# 600_v1_0.net
KiCad netlist of a schematic drawn in Altium Designer
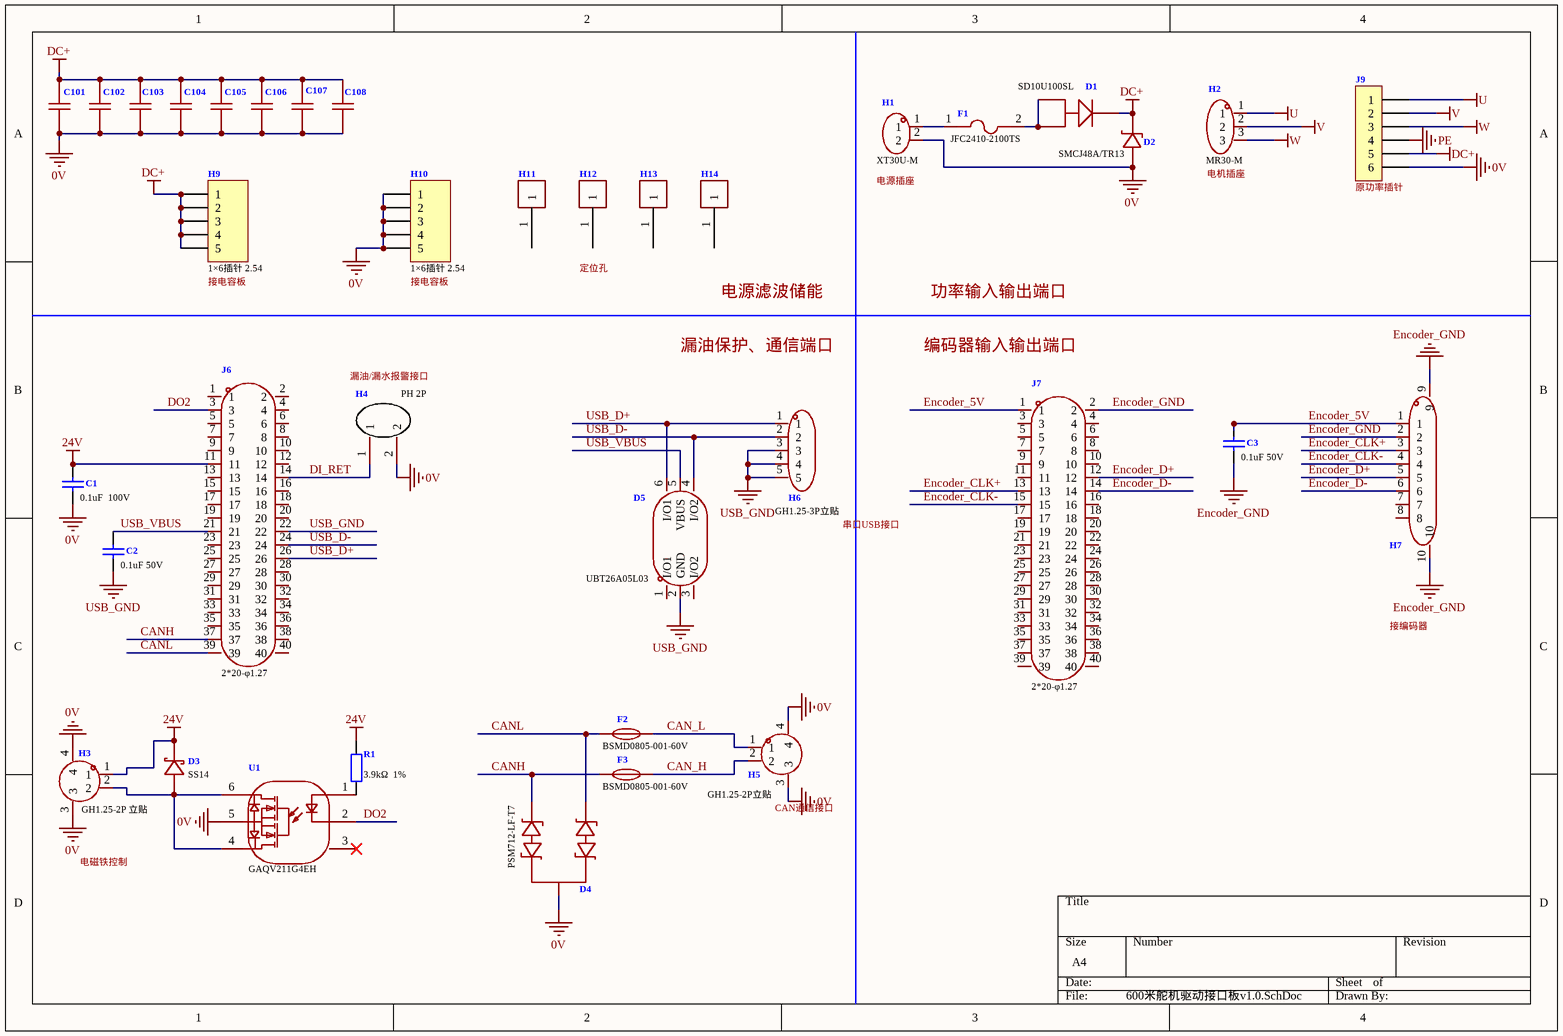
[diagram p0: 600米舵机驱动接口板v1.0.SchDoc]

(export (version "E")
  (design (tool "Eeschema 10.0.6"))
  (components
    (comp (ref "C1")
      (value "0.1uF  100V")
      (footprint "0805_C")
      (description "贴片电容")
      (libsource (lib "Miscellaneous Devices LC") (part "0805 1uF (105) 10% 50V"))
    )
    (comp (ref "C2")
      (value "0.1uF 50V")
      (footprint "0805_C")
      (description "贴片电容")
      (libsource (lib "Miscellaneous Devices LC") (part "0805 1uF (105) 10% 50V"))
    )
    (comp (ref "C3")
      (value "0.1uF 50V")
      (footprint "0805_C")
      (description "贴片电容")
      (libsource (lib "Miscellaneous Devices LC") (part "0805 1uF (105) 10% 50V"))
    )
    (comp (ref "C101")
      (value "4.7uf 100V")
      (footprint "1210_C")
      (description "贴片电容")
      (fields (field (name "MANUFACTURER") "FH(风华)") (field (name "MANUFACTURER PART") "1210B475K101NT"))
      (libsource (lib "Schlib1") (part "1210 4.7uf"))
    )
    (comp (ref "C102")
      (value "4.7uf 100V")
      (footprint "1210_C")
      (description "贴片电容")
      (fields (field (name "MANUFACTURER") "FH(风华)") (field (name "MANUFACTURER PART") "1210B475K101NT"))
      (libsource (lib "Schlib1") (part "1210 4.7uf"))
    )
    (comp (ref "C103")
      (value "4.7uf 100V")
      (footprint "1210_C")
      (description "贴片电容")
      (fields (field (name "MANUFACTURER") "FH(风华)") (field (name "MANUFACTURER PART") "1210B475K101NT"))
      (libsource (lib "Schlib1") (part "1210 4.7uf"))
    )
    (comp (ref "C104")
      (value "4.7uf 100V")
      (footprint "1210_C")
      (description "贴片电容")
      (fields (field (name "MANUFACTURER") "FH(风华)") (field (name "MANUFACTURER PART") "1210B475K101NT"))
      (libsource (lib "Schlib1") (part "1210 4.7uf"))
    )
    (comp (ref "C105")
      (value "4.7uf 100V")
      (footprint "1210_C")
      (description "贴片电容")
      (fields (field (name "MANUFACTURER") "FH(风华)") (field (name "MANUFACTURER PART") "1210B475K101NT"))
      (libsource (lib "Schlib1") (part "1210 4.7uf"))
    )
    (comp (ref "C106")
      (value "4.7uf 100V")
      (footprint "1210_C")
      (description "贴片电容")
      (fields (field (name "MANUFACTURER") "FH(风华)") (field (name "MANUFACTURER PART") "1210B475K101NT"))
      (libsource (lib "Schlib1") (part "1210 4.7uf"))
    )
    (comp (ref "C107")
      (value "4.7uf 100V")
      (footprint "1210_C")
      (description "贴片电容")
      (fields (field (name "MANUFACTURER") "FH(风华)") (field (name "MANUFACTURER PART") "1210B475K101NT"))
      (libsource (lib "Schlib1") (part "1210 4.7uf"))
    )
    (comp (ref "C108")
      (value "4.7uf 100V")
      (footprint "1210_C")
      (description "贴片电容")
      (fields (field (name "MANUFACTURER") "FH(风华)") (field (name "MANUFACTURER PART") "1210B475K101NT"))
      (libsource (lib "Schlib1") (part "1210 4.7uf"))
    )
    (comp (ref "D1")
      (value "SD10U100SL")
      (footprint "TO-227B-SMD_L6.1-W4.3-LS7.0-RD")
      (description "肖特基二极管")
      (fields (field (name "MANUFACTURER") "LGE(鲁光)"))
      (libsource (lib "二极管稳压等") (part "SD10U100SL"))
    )
    (comp (ref "D2")
      (value "SMCJ48A/TR13")
      (footprint "SMC_L7.1-W6.2-LS8.1-FD")
      (description "TVS")
      (fields (field (name "MANUFACTURER") "Brightking(君耀电子)"))
      (libsource (lib "二极管稳压等") (part "SMCJ48A/TR13"))
    )
    (comp (ref "D3")
      (value "SS14")
      (footprint "SMAF_L3.5-W2.6-LS4.7-FD")
      (fields (field (name "MANUFACTURER") "GOODWORK(固得沃克)") (field (name "MANUFACTURER PART") "SS34F"))
      (libsource (lib "Schlib1") (part "SS34F_C908669"))
    )
    (comp (ref "D4")
      (value "PSM712-LF-T7")
      (footprint "SOT-23(SOT-23-3)")
      (description "双向TVS")
      (fields (field (name "MANUFACTURER") "PROTEK"))
      (libsource (lib "二极管稳压等") (part "PSM712-LF-T7"))
    )
    (comp (ref "D5")
      (value "UBT26A05L03")
      (footprint "SOT-23-6_L2.9-W1.6-P0.95-LS2.8-BR")
      (description "TVS")
      (fields (field (name "MANUFACTURER") "Brightking(君耀电子)"))
      (libsource (lib "二极管稳压等") (part "UBT26A05L03"))
    )
    (comp (ref "F1")
      (value "JFC2410-2100TS")
      (footprint "F2410")
      (description "保险管")
      (fields (field (name "MANUFACTURER") "JDTfuse(集电通)"))
      (libsource (lib "保险") (part "JFC2410-2100TS"))
    )
    (comp (ref "F2")
      (value "BSMD0805-001-60V")
      (footprint "F0805")
      (description "自恢复保险")
      (fields (field (name "MANUFACTURER") "BHFUSE(佰宏)"))
      (libsource (lib "保险") (part "BSMD0805-001-60V"))
    )
    (comp (ref "F3")
      (value "BSMD0805-001-60V")
      (footprint "F0805")
      (description "自恢复保险")
      (fields (field (name "MANUFACTURER") "BHFUSE(佰宏)"))
      (libsource (lib "保险") (part "BSMD0805-001-60V"))
    )
    (comp (ref "H1")
      (value "XT30U-M")
      (footprint "CONN-TH_XT30U-M-PCB")
      (fields (field (name "MANUFACTURER") "AMASS(艾迈斯)"))
      (libsource (lib "Header") (part "XT30U-M"))
    )
    (comp (ref "H2")
      (value "MR30-M")
      (footprint "CONN-TH_MR30-M-PCB")
      (fields (field (name "MANUFACTURER") "AMASS(艾迈斯)"))
      (libsource (lib "Header") (part "MR30-M"))
    )
    (comp (ref "H3")
      (value "GH1.25-2P 立贴")
      (footprint "CONN-TH_2P-P1.25_XUNPU_WAFER-GH1.25-2PLB")
      (fields
        (field (name "MANUFACTURER") "XUNPU(讯普)")
        (field (name "MANUFACTURER PART") "WAFER-GH1.25-2PLB")
      )
      (libsource (lib "Header") (part "WAFER-GH1.25-2PLB"))
    )
    (comp (ref "H4")
      (value "PH 2P")
      (footprint "CONN-TH_B2B-PH-K-S")
      (description "端子")
      (fields (field (name "MANUFACTURER") "JST") (field (name "MANUFACTURER PART") "B2B-PH-K-S(LF)(SN)"))
      (libsource (lib "Header") (part "PH2.0-2P"))
    )
    (comp (ref "H5")
      (value "GH1.25-2P立贴")
      (footprint "CONN-TH_2P-P1.25_XUNPU_WAFER-GH1.25-2PLB")
      (description "连接器")
      (fields
        (field (name "MANUFACTURER") "XUNPU(讯普)")
        (field (name "MANUFACTURER PART") "WAFER-GH1.25-2PLB")
      )
      (libsource (lib "Header") (part "WAFER-GH1.25-2PLB"))
    )
    (comp (ref "H6")
      (value "GH1.25-3P立贴")
      (footprint "CONN-SMD_3P-P1.25_GH1.25-3PLTPZ")
      (description "连接器")
      (fields
        (field (name "MANUFACTURER") "BOOMELE(博穆精密)")
        (field (name "MANUFACTURER PART") "GH1.25-3PLTPZ")
      )
      (libsource (lib "Header") (part "GH1.25-3PLTPZ"))
    )
    (comp (ref "H7")
      (value "SM08B-SURS-TF(LF)(SN)")
      (footprint "CONN-SMD_SM08B-SURS-TF")
      (description "连接器")
      (fields (field (name "MANUFACTURER") "JST"))
      (libsource (lib "Header") (part "SM08B-SURS-TF(LF)(SN)"))
    )
    (comp (ref "H9")
      (value "1×6插针 2.54")
      (footprint "HDR1X5")
      (description "Header, 5-Pin")
      (fields (field (name "PUBLISHER") "Altium Limited"))
      (libsource (lib "Miscellaneous Connectors") (part "Header 5"))
    )
    (comp (ref "H10")
      (value "1×6插针 2.54")
      (footprint "HDR1X5")
      (description "Header, 5-Pin")
      (fields (field (name "PUBLISHER") "Altium Limited"))
      (libsource (lib "Miscellaneous Connectors") (part "Header 5"))
    )
    (comp (ref "H11") (value "定位孔") (footprint "Hole-2.5×3.5") (libsource (lib "Other") (part "Hole")))
    (comp (ref "H12") (value "定位孔") (footprint "Hole-2.5×3.5") (libsource (lib "Other") (part "Hole")))
    (comp (ref "H13") (value "定位孔") (footprint "Hole-2.5×3.5") (libsource (lib "Other") (part "Hole")))
    (comp (ref "H14") (value "定位孔") (footprint "Hole-2.5×3.5") (libsource (lib "Other") (part "Hole")))
    (comp (ref "J6")
      (value "2*20-φ1.27")
      (footprint "HDR-TH_40P-P1.27-V-M-R2-C20-S1.27-ISMC")
      (description "插针孔")
      (fields (field (name "MANUFACTURER") "BOOMELE(博穆精密)") (field (name "MANUFACTURER PART") "2.0-2*20PM"))
      (libsource (lib "Schlib1") (part "2.0-2*20PM"))
    )
    (comp (ref "J7")
      (value "2*20-φ1.27")
      (footprint "HDR-TH_40P-P1.27-V-M-R2-C20-S1.27-ISMC")
      (description "插针孔")
      (fields (field (name "MANUFACTURER") "BOOMELE(博穆精密)") (field (name "MANUFACTURER PART") "2.0-2*20PM"))
      (libsource (lib "Schlib1") (part "2.0-2*20PM"))
    )
    (comp (ref "J9")
      (value "φ1.3")
      (footprint "ISMC_Power")
      (description "插针孔")
      (libsource (lib "Header") (part "Pin HDR1X6"))
    )
    (comp (ref "R1")
      (value "3.9kΩ  1%")
      (footprint "0805_R")
      (description "贴片电阻")
      (libsource (lib "电阻") (part "0805 82Ω (82R0) 1%"))
    )
    (comp (ref "U1")
      (value "GAQV211G4EH")
      (footprint "SMD-6_L8.8-W6.4-P2.54-LS9.6-BL")
      (fields (field (name "MANUFACTURER") "SUPSiC(国晶微半导体)"))
      (libsource (lib "继电器") (part "GAQV211G4EH"))
    )
  )
  (nets
    (net (code "1") (name "/CANH") (class "Default")
      (node (ref "D4") (pin "2") (pinfunction "A1_2") (pintype "passive"))
      (node (ref "F3") (pin "1") (pinfunction "1_1") (pintype "passive"))
      (node (ref "J6") (pin "37") (pinfunction "37_37") (pintype "passive"))
    )
    (net (code "2") (name "/CANL") (class "Default")
      (node (ref "D4") (pin "1") (pinfunction "A1_1") (pintype "passive"))
      (node (ref "F2") (pin "1") (pinfunction "1_1") (pintype "passive"))
      (node (ref "J6") (pin "39") (pinfunction "39_39") (pintype "passive"))
    )
    (net (code "3") (name "/CAN_H") (class "Default")
      (node (ref "F3") (pin "2") (pinfunction "2_2") (pintype "passive"))
      (node (ref "H5") (pin "2") (pinfunction "2_2") (pintype "passive"))
    )
    (net (code "4") (name "/CAN_L") (class "Default")
      (node (ref "F2") (pin "2") (pinfunction "2_2") (pintype "passive"))
      (node (ref "H5") (pin "1") (pinfunction "1_1") (pintype "passive"))
    )
    (net (code "5") (name "/DI_RET") (class "Default")
      (node (ref "H4") (pin "1") (pinfunction "1_1") (pintype "passive"))
      (node (ref "J6") (pin "14") (pinfunction "14_14") (pintype "passive"))
    )
    (net (code "6") (name "/DO2") (class "Default")
      (node (ref "J6") (pin "3") (pinfunction "3_3") (pintype "passive"))
      (node (ref "U1") (pin "2") (pinfunction "2_2") (pintype "passive"))
    )
    (net (code "7") (name "/Encoder_5V") (class "Default")
      (node (ref "C3") (pin "2") (pinfunction "2_2") (pintype "passive"))
      (node (ref "H7") (pin "1") (pinfunction "1_1") (pintype "passive"))
      (node (ref "J7") (pin "1") (pinfunction "1_1") (pintype "passive"))
    )
    (net (code "8") (name "/Encoder_CLK+") (class "Default")
      (node (ref "H7") (pin "3") (pinfunction "3_3") (pintype "passive"))
      (node (ref "J7") (pin "13") (pinfunction "13_13") (pintype "passive"))
    )
    (net (code "9") (name "/Encoder_CLK-") (class "Default")
      (node (ref "H7") (pin "4") (pinfunction "4_4") (pintype "passive"))
      (node (ref "J7") (pin "15") (pinfunction "15_15") (pintype "passive"))
    )
    (net (code "10") (name "/Encoder_D+") (class "Default")
      (node (ref "H7") (pin "5") (pinfunction "5_5") (pintype "passive"))
      (node (ref "J7") (pin "12") (pinfunction "12_12") (pintype "passive"))
    )
    (net (code "11") (name "/Encoder_D-") (class "Default")
      (node (ref "H7") (pin "6") (pinfunction "6_6") (pintype "passive"))
      (node (ref "J7") (pin "14") (pinfunction "14_14") (pintype "passive"))
    )
    (net (code "12") (name "/USB_D+") (class "Default")
      (node (ref "D5") (pin "6") (pinfunction "I/O1_6") (pintype "passive"))
      (node (ref "H6") (pin "1") (pinfunction "1_1") (pintype "passive"))
      (node (ref "J6") (pin "26") (pinfunction "26_26") (pintype "passive"))
    )
    (net (code "13") (name "/USB_D-") (class "Default")
      (node (ref "D5") (pin "4") (pinfunction "I/O2_4") (pintype "passive"))
      (node (ref "H6") (pin "2") (pinfunction "2_2") (pintype "passive"))
      (node (ref "J6") (pin "24") (pinfunction "24_24") (pintype "passive"))
    )
    (net (code "14") (name "/USB_VBUS") (class "Default")
      (node (ref "C2") (pin "2") (pinfunction "2_2") (pintype "passive"))
      (node (ref "D5") (pin "5") (pinfunction "VBUS_5") (pintype "passive"))
      (node (ref "J6") (pin "21") (pinfunction "21_21") (pintype "passive"))
    )
    (net (code "15") (name "0V") (class "Default")
      (node (ref "C1") (pin "1") (pinfunction "1_1") (pintype "passive"))
      (node (ref "C101") (pin "1") (pinfunction "1_1") (pintype "passive"))
      (node (ref "C102") (pin "1") (pinfunction "1_1") (pintype "passive"))
      (node (ref "C103") (pin "1") (pinfunction "1_1") (pintype "passive"))
      (node (ref "C104") (pin "1") (pinfunction "1_1") (pintype "passive"))
      (node (ref "C105") (pin "1") (pinfunction "1_1") (pintype "passive"))
      (node (ref "C106") (pin "1") (pinfunction "1_1") (pintype "passive"))
      (node (ref "C107") (pin "1") (pinfunction "1_1") (pintype "passive"))
      (node (ref "C108") (pin "1") (pinfunction "1_1") (pintype "passive"))
      (node (ref "D2") (pin "1") (pinfunction "A_1") (pintype "passive"))
      (node (ref "D4") (pin "3") (pinfunction "K_3") (pintype "passive"))
      (node (ref "H1") (pin "2") (pinfunction "2_2") (pintype "passive"))
      (node (ref "H10") (pin "1") (pinfunction "1_1") (pintype "passive"))
      (node (ref "H10") (pin "2") (pinfunction "2_2") (pintype "passive"))
      (node (ref "H10") (pin "3") (pinfunction "3_3") (pintype "passive"))
      (node (ref "H10") (pin "4") (pinfunction "4_4") (pintype "passive"))
      (node (ref "H10") (pin "5") (pinfunction "5_5") (pintype "passive"))
      (node (ref "H3") (pin "3") (pinfunction "3_3") (pintype "passive"))
      (node (ref "H3") (pin "4") (pinfunction "4_4") (pintype "passive"))
      (node (ref "H4") (pin "2") (pinfunction "2_2") (pintype "passive"))
      (node (ref "H5") (pin "3") (pinfunction "3_3") (pintype "passive"))
      (node (ref "H5") (pin "4") (pinfunction "4_4") (pintype "passive"))
      (node (ref "J9") (pin "6") (pinfunction "6_6") (pintype "passive"))
      (node (ref "U1") (pin "5") (pinfunction "5_5") (pintype "passive"))
    )
    (net (code "16") (name "24V") (class "Default")
      (node (ref "C1") (pin "2") (pinfunction "2_2") (pintype "passive"))
      (node (ref "D3") (pin "2") (pinfunction "K_2") (pintype "passive"))
      (node (ref "H3") (pin "1") (pinfunction "1_1") (pintype "passive"))
      (node (ref "J6") (pin "11") (pinfunction "11_11") (pintype "passive"))
      (node (ref "R1") (pin "1") (pinfunction "1_1") (pintype "passive"))
    )
    (net (code "17") (name "DC+") (class "Default")
      (node (ref "C101") (pin "2") (pinfunction "2_2") (pintype "passive"))
      (node (ref "C102") (pin "2") (pinfunction "2_2") (pintype "passive"))
      (node (ref "C103") (pin "2") (pinfunction "2_2") (pintype "passive"))
      (node (ref "C104") (pin "2") (pinfunction "2_2") (pintype "passive"))
      (node (ref "C105") (pin "2") (pinfunction "2_2") (pintype "passive"))
      (node (ref "C106") (pin "2") (pinfunction "2_2") (pintype "passive"))
      (node (ref "C107") (pin "2") (pinfunction "2_2") (pintype "passive"))
      (node (ref "C108") (pin "2") (pinfunction "2_2") (pintype "passive"))
      (node (ref "D1") (pin "3") (pinfunction "3_3") (pintype "passive"))
      (node (ref "D2") (pin "2") (pinfunction "K_2") (pintype "passive"))
      (node (ref "H9") (pin "1") (pinfunction "1_1") (pintype "passive"))
      (node (ref "H9") (pin "2") (pinfunction "2_2") (pintype "passive"))
      (node (ref "H9") (pin "3") (pinfunction "3_3") (pintype "passive"))
      (node (ref "H9") (pin "4") (pinfunction "4_4") (pintype "passive"))
      (node (ref "H9") (pin "5") (pinfunction "5_5") (pintype "passive"))
      (node (ref "J9") (pin "5") (pinfunction "5_5") (pintype "passive"))
    )
    (net (code "18") (name "Encoder_GND") (class "Default")
      (node (ref "C3") (pin "1") (pinfunction "1_1") (pintype "passive"))
      (node (ref "H7") (pin "10") (pinfunction "10_10") (pintype "passive"))
      (node (ref "H7") (pin "2") (pinfunction "2_2") (pintype "passive"))
      (node (ref "H7") (pin "9") (pinfunction "9_9") (pintype "passive"))
      (node (ref "J7") (pin "2") (pinfunction "2_2") (pintype "passive"))
    )
    (net (code "19") (name "Net-(D1-Pad1)") (class "Default")
      (node (ref "D1") (pin "1") (pinfunction "1_1") (pintype "passive"))
      (node (ref "D1") (pin "2") (pinfunction "2_2") (pintype "passive"))
      (node (ref "F1") (pin "2") (pinfunction "2_2") (pintype "passive"))
    )
    (net (code "20") (name "Net-(D3-A)") (class "Default")
      (node (ref "D3") (pin "1") (pinfunction "A_1") (pintype "passive"))
      (node (ref "H3") (pin "2") (pinfunction "2_2") (pintype "passive"))
      (node (ref "U1") (pin "4") (pinfunction "4_4") (pintype "passive"))
      (node (ref "U1") (pin "6") (pinfunction "6_6") (pintype "passive"))
    )
    (net (code "21") (name "Net-(F1-Pad1)") (class "Default")
      (node (ref "F1") (pin "1") (pinfunction "1_1") (pintype "passive"))
      (node (ref "H1") (pin "1") (pinfunction "1_1") (pintype "passive"))
    )
    (net (code "22") (name "Net-(R1-Pad2)") (class "Default")
      (node (ref "R1") (pin "2") (pinfunction "2_2") (pintype "passive"))
      (node (ref "U1") (pin "1") (pinfunction "1_1") (pintype "passive"))
    )
    (net (code "23") (name "PE") (class "Default")
      (node (ref "J9") (pin "4") (pinfunction "4_4") (pintype "passive"))
    )
    (net (code "24") (name "U") (class "Default")
      (node (ref "H2") (pin "1") (pinfunction "1_1") (pintype "passive"))
      (node (ref "J9") (pin "1") (pinfunction "1_1") (pintype "passive"))
    )
    (net (code "25") (name "USB_GND") (class "Default")
      (node (ref "C2") (pin "1") (pinfunction "1_1") (pintype "passive"))
      (node (ref "D5") (pin "2") (pinfunction "GND_2") (pintype "passive"))
      (node (ref "H6") (pin "3") (pinfunction "3_3") (pintype "passive"))
      (node (ref "H6") (pin "4") (pinfunction "4_4") (pintype "passive"))
      (node (ref "H6") (pin "5") (pinfunction "5_5") (pintype "passive"))
      (node (ref "J6") (pin "22") (pinfunction "22_22") (pintype "passive"))
    )
    (net (code "26") (name "V") (class "Default")
      (node (ref "H2") (pin "2") (pinfunction "2_2") (pintype "passive"))
      (node (ref "J9") (pin "2") (pinfunction "2_2") (pintype "passive"))
    )
    (net (code "27") (name "W") (class "Default")
      (node (ref "H2") (pin "3") (pinfunction "3_3") (pintype "passive"))
      (node (ref "J9") (pin "3") (pinfunction "3_3") (pintype "passive"))
    )
    (net (code "28") (name "unconnected-(D5-I{slash}O1-Pad1)") (class "Default")
      (node (ref "D5") (pin "1") (pinfunction "I/O1_1") (pintype "passive"))
    )
    (net (code "29") (name "unconnected-(D5-I{slash}O2-Pad3)") (class "Default")
      (node (ref "D5") (pin "3") (pinfunction "I/O2_3") (pintype "passive"))
    )
    (net (code "30") (name "unconnected-(H7-Pad7)") (class "Default")
      (node (ref "H7") (pin "7") (pinfunction "7_7") (pintype "passive"))
    )
    (net (code "31") (name "unconnected-(H7-Pad8)") (class "Default")
      (node (ref "H7") (pin "8") (pinfunction "8_8") (pintype "passive"))
    )
    (net (code "32") (name "unconnected-(H11-Pad1)") (class "Default")
      (node (ref "H11") (pin "1") (pinfunction "1_1") (pintype "passive"))
    )
    (net (code "33") (name "unconnected-(H12-Pad1)") (class "Default")
      (node (ref "H12") (pin "1") (pinfunction "1_1") (pintype "passive"))
    )
    (net (code "34") (name "unconnected-(H13-Pad1)") (class "Default")
      (node (ref "H13") (pin "1") (pinfunction "1_1") (pintype "passive"))
    )
    (net (code "35") (name "unconnected-(H14-Pad1)") (class "Default")
      (node (ref "H14") (pin "1") (pinfunction "1_1") (pintype "passive"))
    )
    (net (code "36") (name "unconnected-(J6-Pad1)") (class "Default")
      (node (ref "J6") (pin "1") (pinfunction "1_1") (pintype "passive"))
    )
    (net (code "37") (name "unconnected-(J6-Pad2)") (class "Default")
      (node (ref "J6") (pin "2") (pinfunction "2_2") (pintype "passive"))
    )
    (net (code "38") (name "unconnected-(J6-Pad4)") (class "Default")
      (node (ref "J6") (pin "4") (pinfunction "4_4") (pintype "passive"))
    )
    (net (code "39") (name "unconnected-(J6-Pad5)") (class "Default")
      (node (ref "J6") (pin "5") (pinfunction "5_5") (pintype "passive"))
    )
    (net (code "40") (name "unconnected-(J6-Pad6)") (class "Default")
      (node (ref "J6") (pin "6") (pinfunction "6_6") (pintype "passive"))
    )
    (net (code "41") (name "unconnected-(J6-Pad7)") (class "Default")
      (node (ref "J6") (pin "7") (pinfunction "7_7") (pintype "passive"))
    )
    (net (code "42") (name "unconnected-(J6-Pad8)") (class "Default")
      (node (ref "J6") (pin "8") (pinfunction "8_8") (pintype "passive"))
    )
    (net (code "43") (name "unconnected-(J6-Pad9)") (class "Default")
      (node (ref "J6") (pin "9") (pinfunction "9_9") (pintype "passive"))
    )
    (net (code "44") (name "unconnected-(J6-Pad10)") (class "Default")
      (node (ref "J6") (pin "10") (pinfunction "10_10") (pintype "passive"))
    )
    (net (code "45") (name "unconnected-(J6-Pad12)") (class "Default")
      (node (ref "J6") (pin "12") (pinfunction "12_12") (pintype "passive"))
    )
    (net (code "46") (name "unconnected-(J6-Pad13)") (class "Default")
      (node (ref "J6") (pin "13") (pinfunction "13_13") (pintype "passive"))
    )
    (net (code "47") (name "unconnected-(J6-Pad15)") (class "Default")
      (node (ref "J6") (pin "15") (pinfunction "15_15") (pintype "passive"))
    )
    (net (code "48") (name "unconnected-(J6-Pad16)") (class "Default")
      (node (ref "J6") (pin "16") (pinfunction "16_16") (pintype "passive"))
    )
    (net (code "49") (name "unconnected-(J6-Pad17)") (class "Default")
      (node (ref "J6") (pin "17") (pinfunction "17_17") (pintype "passive"))
    )
    (net (code "50") (name "unconnected-(J6-Pad18)") (class "Default")
      (node (ref "J6") (pin "18") (pinfunction "18_18") (pintype "passive"))
    )
    (net (code "51") (name "unconnected-(J6-Pad19)") (class "Default")
      (node (ref "J6") (pin "19") (pinfunction "19_19") (pintype "passive"))
    )
    (net (code "52") (name "unconnected-(J6-Pad20)") (class "Default")
      (node (ref "J6") (pin "20") (pinfunction "20_20") (pintype "passive"))
    )
    (net (code "53") (name "unconnected-(J6-Pad23)") (class "Default")
      (node (ref "J6") (pin "23") (pinfunction "23_23") (pintype "passive"))
    )
    (net (code "54") (name "unconnected-(J6-Pad25)") (class "Default")
      (node (ref "J6") (pin "25") (pinfunction "25_25") (pintype "passive"))
    )
    (net (code "55") (name "unconnected-(J6-Pad27)") (class "Default")
      (node (ref "J6") (pin "27") (pinfunction "27_27") (pintype "passive"))
    )
    (net (code "56") (name "unconnected-(J6-Pad28)") (class "Default")
      (node (ref "J6") (pin "28") (pinfunction "28_28") (pintype "passive"))
    )
    (net (code "57") (name "unconnected-(J6-Pad29)") (class "Default")
      (node (ref "J6") (pin "29") (pinfunction "29_29") (pintype "passive"))
    )
    (net (code "58") (name "unconnected-(J6-Pad30)") (class "Default")
      (node (ref "J6") (pin "30") (pinfunction "30_30") (pintype "passive"))
    )
    (net (code "59") (name "unconnected-(J6-Pad31)") (class "Default")
      (node (ref "J6") (pin "31") (pinfunction "31_31") (pintype "passive"))
    )
    (net (code "60") (name "unconnected-(J6-Pad32)") (class "Default")
      (node (ref "J6") (pin "32") (pinfunction "32_32") (pintype "passive"))
    )
    (net (code "61") (name "unconnected-(J6-Pad33)") (class "Default")
      (node (ref "J6") (pin "33") (pinfunction "33_33") (pintype "passive"))
    )
    (net (code "62") (name "unconnected-(J6-Pad34)") (class "Default")
      (node (ref "J6") (pin "34") (pinfunction "34_34") (pintype "passive"))
    )
    (net (code "63") (name "unconnected-(J6-Pad35)") (class "Default")
      (node (ref "J6") (pin "35") (pinfunction "35_35") (pintype "passive"))
    )
    (net (code "64") (name "unconnected-(J6-Pad36)") (class "Default")
      (node (ref "J6") (pin "36") (pinfunction "36_36") (pintype "passive"))
    )
    (net (code "65") (name "unconnected-(J6-Pad38)") (class "Default")
      (node (ref "J6") (pin "38") (pinfunction "38_38") (pintype "passive"))
    )
    (net (code "66") (name "unconnected-(J6-Pad40)") (class "Default")
      (node (ref "J6") (pin "40") (pinfunction "40_40") (pintype "passive"))
    )
    (net (code "67") (name "unconnected-(J7-Pad3)") (class "Default")
      (node (ref "J7") (pin "3") (pinfunction "3_3") (pintype "passive"))
    )
    (net (code "68") (name "unconnected-(J7-Pad4)") (class "Default")
      (node (ref "J7") (pin "4") (pinfunction "4_4") (pintype "passive"))
    )
    (net (code "69") (name "unconnected-(J7-Pad5)") (class "Default")
      (node (ref "J7") (pin "5") (pinfunction "5_5") (pintype "passive"))
    )
    (net (code "70") (name "unconnected-(J7-Pad6)") (class "Default")
      (node (ref "J7") (pin "6") (pinfunction "6_6") (pintype "passive"))
    )
    (net (code "71") (name "unconnected-(J7-Pad7)") (class "Default")
      (node (ref "J7") (pin "7") (pinfunction "7_7") (pintype "passive"))
    )
    (net (code "72") (name "unconnected-(J7-Pad8)") (class "Default")
      (node (ref "J7") (pin "8") (pinfunction "8_8") (pintype "passive"))
    )
    (net (code "73") (name "unconnected-(J7-Pad9)") (class "Default")
      (node (ref "J7") (pin "9") (pinfunction "9_9") (pintype "passive"))
    )
    (net (code "74") (name "unconnected-(J7-Pad10)") (class "Default")
      (node (ref "J7") (pin "10") (pinfunction "10_10") (pintype "passive"))
    )
    (net (code "75") (name "unconnected-(J7-Pad11)") (class "Default")
      (node (ref "J7") (pin "11") (pinfunction "11_11") (pintype "passive"))
    )
    (net (code "76") (name "unconnected-(J7-Pad16)") (class "Default")
      (node (ref "J7") (pin "16") (pinfunction "16_16") (pintype "passive"))
    )
    (net (code "77") (name "unconnected-(J7-Pad17)") (class "Default")
      (node (ref "J7") (pin "17") (pinfunction "17_17") (pintype "passive"))
    )
    (net (code "78") (name "unconnected-(J7-Pad18)") (class "Default")
      (node (ref "J7") (pin "18") (pinfunction "18_18") (pintype "passive"))
    )
    (net (code "79") (name "unconnected-(J7-Pad19)") (class "Default")
      (node (ref "J7") (pin "19") (pinfunction "19_19") (pintype "passive"))
    )
    (net (code "80") (name "unconnected-(J7-Pad20)") (class "Default")
      (node (ref "J7") (pin "20") (pinfunction "20_20") (pintype "passive"))
    )
    (net (code "81") (name "unconnected-(J7-Pad21)") (class "Default")
      (node (ref "J7") (pin "21") (pinfunction "21_21") (pintype "passive"))
    )
    (net (code "82") (name "unconnected-(J7-Pad22)") (class "Default")
      (node (ref "J7") (pin "22") (pinfunction "22_22") (pintype "passive"))
    )
    (net (code "83") (name "unconnected-(J7-Pad23)") (class "Default")
      (node (ref "J7") (pin "23") (pinfunction "23_23") (pintype "passive"))
    )
    (net (code "84") (name "unconnected-(J7-Pad24)") (class "Default")
      (node (ref "J7") (pin "24") (pinfunction "24_24") (pintype "passive"))
    )
    (net (code "85") (name "unconnected-(J7-Pad25)") (class "Default")
      (node (ref "J7") (pin "25") (pinfunction "25_25") (pintype "passive"))
    )
    (net (code "86") (name "unconnected-(J7-Pad26)") (class "Default")
      (node (ref "J7") (pin "26") (pinfunction "26_26") (pintype "passive"))
    )
    (net (code "87") (name "unconnected-(J7-Pad27)") (class "Default")
      (node (ref "J7") (pin "27") (pinfunction "27_27") (pintype "passive"))
    )
    (net (code "88") (name "unconnected-(J7-Pad28)") (class "Default")
      (node (ref "J7") (pin "28") (pinfunction "28_28") (pintype "passive"))
    )
    (net (code "89") (name "unconnected-(J7-Pad29)") (class "Default")
      (node (ref "J7") (pin "29") (pinfunction "29_29") (pintype "passive"))
    )
    (net (code "90") (name "unconnected-(J7-Pad30)") (class "Default")
      (node (ref "J7") (pin "30") (pinfunction "30_30") (pintype "passive"))
    )
    (net (code "91") (name "unconnected-(J7-Pad31)") (class "Default")
      (node (ref "J7") (pin "31") (pinfunction "31_31") (pintype "passive"))
    )
    (net (code "92") (name "unconnected-(J7-Pad32)") (class "Default")
      (node (ref "J7") (pin "32") (pinfunction "32_32") (pintype "passive"))
    )
    (net (code "93") (name "unconnected-(J7-Pad33)") (class "Default")
      (node (ref "J7") (pin "33") (pinfunction "33_33") (pintype "passive"))
    )
    (net (code "94") (name "unconnected-(J7-Pad34)") (class "Default")
      (node (ref "J7") (pin "34") (pinfunction "34_34") (pintype "passive"))
    )
    (net (code "95") (name "unconnected-(J7-Pad35)") (class "Default")
      (node (ref "J7") (pin "35") (pinfunction "35_35") (pintype "passive"))
    )
    (net (code "96") (name "unconnected-(J7-Pad36)") (class "Default")
      (node (ref "J7") (pin "36") (pinfunction "36_36") (pintype "passive"))
    )
    (net (code "97") (name "unconnected-(J7-Pad37)") (class "Default")
      (node (ref "J7") (pin "37") (pinfunction "37_37") (pintype "passive"))
    )
    (net (code "98") (name "unconnected-(J7-Pad38)") (class "Default")
      (node (ref "J7") (pin "38") (pinfunction "38_38") (pintype "passive"))
    )
    (net (code "99") (name "unconnected-(J7-Pad39)") (class "Default")
      (node (ref "J7") (pin "39") (pinfunction "39_39") (pintype "passive"))
    )
    (net (code "100") (name "unconnected-(J7-Pad40)") (class "Default")
      (node (ref "J7") (pin "40") (pinfunction "40_40") (pintype "passive"))
    )
    (net (code "101") (name "unconnected-(U1-Pad3)") (class "Default")
      (node (ref "U1") (pin "3") (pinfunction "3_3") (pintype "passive+no_connect"))
    )
  )
)
